# TK-BB-MD-07_vb.net
KiCad netlist of a schematic drawn in EAGLE
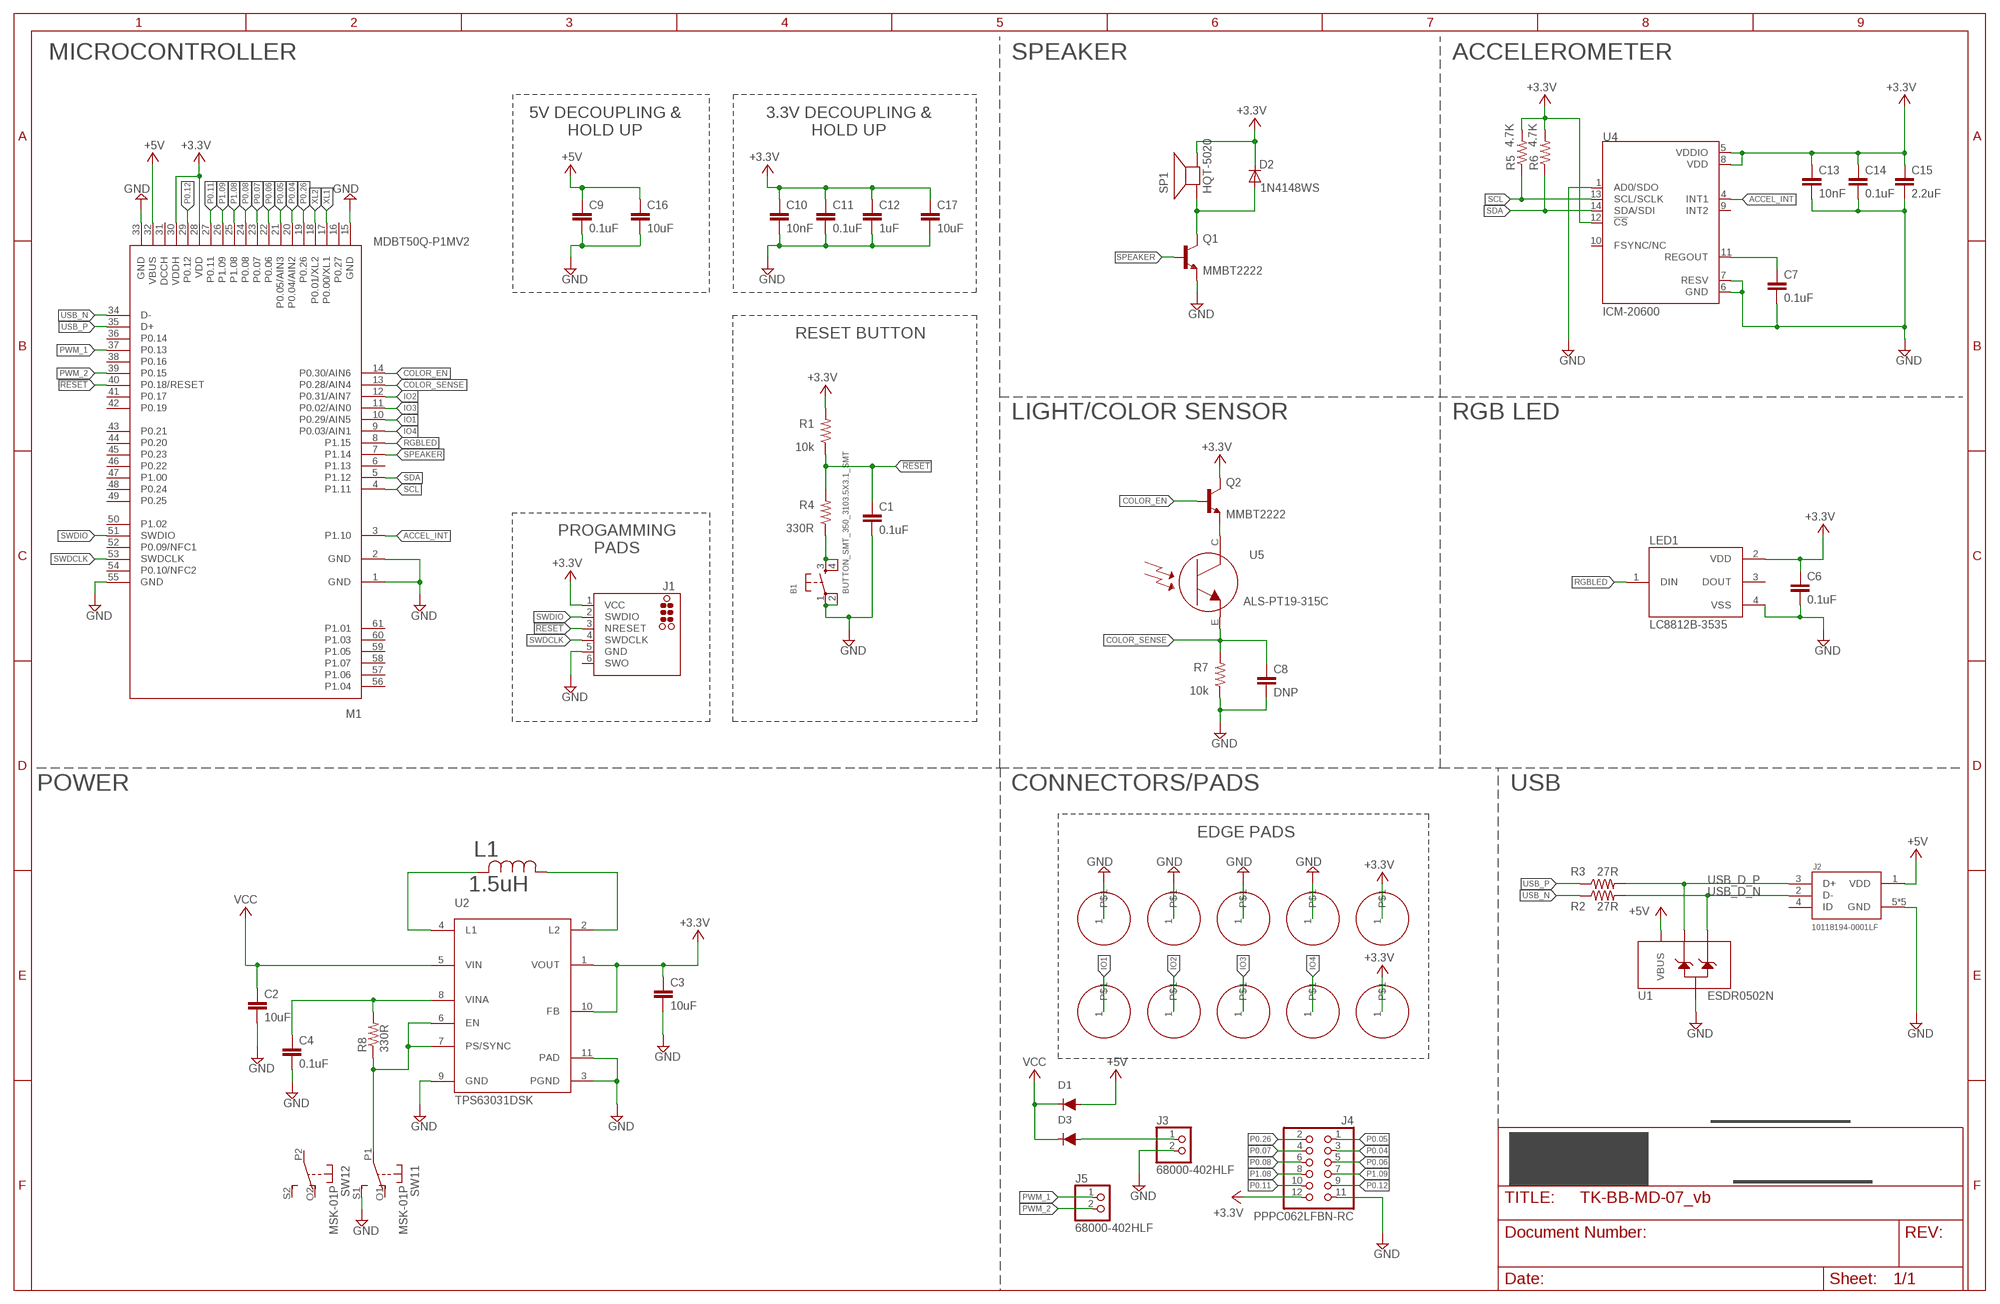
[diagram p0: schematic, sheet 1]

(export (version "E")
  (design (tool "Eeschema 10.0.6"))
  (components
    (comp (ref "B1")
      (value "BUTTON_SMT_350_3103.5X3.1_SMT")
      (footprint "eagle-import:3.5X3.1_SMT")
      (libsource (lib "eagle-import") (part "BUTTON_SMT_350_3103.5X3.1_SMT"))
    )
    (comp (ref "C1")
      (value "0.1uF")
      (footprint "eagle-import:0402")
      (fields
        (field (name "MANUFACTURER") "Yageo")
        (field (name "MANUFACTURER_PART_NUMBER") "CC0402KRX7R6BB104")
      )
      (libsource (lib "eagle-import") (part "C_0402_0.1UF_10V"))
    )
    (comp (ref "C2")
      (value "10uF")
      (footprint "eagle-import:0402")
      (fields
        (field (name "MANUFACTURER") "Samsung")
        (field (name "MANUFACTURER_PART_NUMBER") "CL05A106MP8NUB8")
      )
      (libsource (lib "eagle-import") (part "C_0402_10UF_10V"))
    )
    (comp (ref "C3")
      (value "10uF")
      (footprint "eagle-import:0402")
      (fields
        (field (name "MANUFACTURER") "Samsung")
        (field (name "MANUFACTURER_PART_NUMBER") "CL05A106MP8NUB8")
      )
      (libsource (lib "eagle-import") (part "C_0402_10UF_10V"))
    )
    (comp (ref "C4")
      (value "0.1uF")
      (footprint "eagle-import:0402")
      (fields
        (field (name "MANUFACTURER") "Yageo")
        (field (name "MANUFACTURER_PART_NUMBER") "CC0402KRX7R6BB104")
      )
      (libsource (lib "eagle-import") (part "C_0402_0.1UF_10V"))
    )
    (comp (ref "C6")
      (value "0.1uF")
      (footprint "eagle-import:0402")
      (fields
        (field (name "MANUFACTURER") "Yageo")
        (field (name "MANUFACTURER_PART_NUMBER") "CC0402KRX7R6BB104")
      )
      (libsource (lib "eagle-import") (part "C_0402_0.1UF_10V"))
    )
    (comp (ref "C7")
      (value "0.1uF")
      (footprint "eagle-import:0402")
      (fields
        (field (name "MANUFACTURER") "Yageo")
        (field (name "MANUFACTURER_PART_NUMBER") "CC0402KRX7R6BB104")
      )
      (libsource (lib "eagle-import") (part "C_0402_0.1UF_10V"))
    )
    (comp (ref "C8")
      (value "DNP")
      (footprint "eagle-import:0402")
      (libsource (lib "eagle-import") (part "C_0402_DNP"))
    )
    (comp (ref "C9")
      (value "0.1uF")
      (footprint "eagle-import:0402")
      (fields
        (field (name "MANUFACTURER") "Yageo")
        (field (name "MANUFACTURER_PART_NUMBER") "CC0402KRX7R6BB104")
      )
      (libsource (lib "eagle-import") (part "C_0402_0.1UF_10V"))
    )
    (comp (ref "C10")
      (value "10nF")
      (footprint "eagle-import:0402")
      (fields
        (field (name "MANUFACTURER") "Yageo")
        (field (name "MANUFACTURER_PART_NUMBER") "C0402C103K8RACTU")
      )
      (libsource (lib "eagle-import") (part "C_0402_10NF_10V"))
    )
    (comp (ref "C11")
      (value "0.1uF")
      (footprint "eagle-import:0402")
      (fields
        (field (name "MANUFACTURER") "Yageo")
        (field (name "MANUFACTURER_PART_NUMBER") "CC0402KRX7R6BB104")
      )
      (libsource (lib "eagle-import") (part "C_0402_0.1UF_10V"))
    )
    (comp (ref "C12")
      (value "1uF")
      (footprint "eagle-import:0402")
      (fields
        (field (name "MANUFACTURER") "Yageo")
        (field (name "MANUFACTURER_PART_NUMBER") "CC0402KRX5R6BB105")
      )
      (libsource (lib "eagle-import") (part "C_0402_1UF_10V"))
    )
    (comp (ref "C13")
      (value "10nF")
      (footprint "eagle-import:0402")
      (fields
        (field (name "MANUFACTURER") "Yageo")
        (field (name "MANUFACTURER_PART_NUMBER") "C0402C103K8RACTU")
      )
      (libsource (lib "eagle-import") (part "C_0402_10NF_10V"))
    )
    (comp (ref "C14")
      (value "0.1uF")
      (footprint "eagle-import:0402")
      (fields
        (field (name "MANUFACTURER") "Yageo")
        (field (name "MANUFACTURER_PART_NUMBER") "CC0402KRX7R6BB104")
      )
      (libsource (lib "eagle-import") (part "C_0402_0.1UF_10V"))
    )
    (comp (ref "C15")
      (value "2.2uF")
      (footprint "eagle-import:0402")
      (fields
        (field (name "MANUFACTURER") "Taiyo Yuden")
        (field (name "MANUFACTURER_PART_NUMBER") "LMK105BJ225MV-F")
      )
      (libsource (lib "eagle-import") (part "C_0402_2.2UF_10V"))
    )
    (comp (ref "C16")
      (value "10uF")
      (footprint "eagle-import:0402")
      (fields
        (field (name "MANUFACTURER") "Samsung")
        (field (name "MANUFACTURER_PART_NUMBER") "CL05A106MP8NUB8")
      )
      (libsource (lib "eagle-import") (part "C_0402_10UF_10V"))
    )
    (comp (ref "C17")
      (value "10uF")
      (footprint "eagle-import:0402")
      (fields
        (field (name "MANUFACTURER") "Samsung")
        (field (name "MANUFACTURER_PART_NUMBER") "CL05A106MP8NUB8")
      )
      (libsource (lib "eagle-import") (part "C_0402_10UF_10V"))
    )
    (comp (ref "D1")
      (value "NSR0320MW2T1G")
      (footprint "eagle-import:SOD323")
      (fields (field (name "MANUFACTURER") "ON Semiconductor"))
      (libsource (lib "eagle-import") (part "DIODE_SCHOTTKY_NSR0320MW2T1G"))
    )
    (comp (ref "D2")
      (value "1N4148WS")
      (footprint "eagle-import:SOD-323")
      (fields (field (name "MANUFACTURER") "ON Semiconductor"))
      (libsource (lib "eagle-import") (part "DIODESOD-323_1N148WS"))
    )
    (comp (ref "D3")
      (value "NSR0320MW2T1G")
      (footprint "eagle-import:SOD323")
      (fields (field (name "MANUFACTURER") "ON Semiconductor"))
      (libsource (lib "eagle-import") (part "DIODE_SCHOTTKY_NSR0320MW2T1G"))
    )
    (comp (ref "J1")
      (value "DNP")
      (footprint "eagle-import:TC2030-MCP-NL")
      (libsource (lib "eagle-import") (part "TC2030-MCP-NL"))
    )
    (comp (ref "J2")
      (value "10118194-0001LF")
      (footprint "eagle-import:10118194-0001LF")
      (fields (field (name "MANUFACTURER") "Amphenol"))
      (libsource (lib "eagle-import") (part "10118194-0001LF"))
    )
    (comp (ref "J3")
      (value "68000-402HLF")
      (footprint "eagle-import:1X02")
      (fields (field (name "MANUFACTURER") "Amphenol"))
      (libsource (lib "eagle-import") (part "PINHD-1X2"))
    )
    (comp (ref "J4")
      (value "PPPC062LFBN-RC")
      (footprint "eagle-import:2X06-F")
      (fields (field (name "MANUFACTURER") "Sullins Connector Solutions"))
      (libsource (lib "eagle-import") (part "PINHD-2X6-F"))
    )
    (comp (ref "J5")
      (value "68000-402HLF")
      (footprint "eagle-import:1X02")
      (fields (field (name "MANUFACTURER") "Amphenol"))
      (libsource (lib "eagle-import") (part "PINHD-1X2"))
    )
    (comp (ref "L1")
      (value "1.5uH")
      (footprint "eagle-import:INDC250X200X100")
      (fields
        (field (name "MANUFACTURER") "Delta Electronics/Cyntec")
        (field (name "MANUFACTURER_PART_NUMBER") "SDEM25201T-1R5MS")
      )
      (libsource (lib "eagle-import") (part "SDEM25201T-1R5MS"))
    )
    (comp (ref "LED1")
      (value "LC8812B-3535")
      (footprint "eagle-import:LC8812B-3535")
      (libsource (lib "eagle-import") (part "SK6812MINI_LC8812B-3535"))
    )
    (comp (ref "M1")
      (value "MDBT50Q-P1MV2")
      (footprint "eagle-import:MDBT50")
      (fields (field (name "MANUFACTURER") "Raytac"))
      (libsource (lib "eagle-import") (part "MDBT50Q-P1MV2"))
    )
    (comp (ref "P1")
      (value "BB_PADS_BANANA_ROUND")
      (footprint "eagle-import:BB_PAD_BANANA")
      (libsource (lib "eagle-import") (part "BB_PADS_BANANA_ROUND"))
    )
    (comp (ref "P2")
      (value "BB_PADS_BANANA_ROUND")
      (footprint "eagle-import:BB_PAD_BANANA")
      (libsource (lib "eagle-import") (part "BB_PADS_BANANA_ROUND"))
    )
    (comp (ref "P3")
      (value "BB_PADS_BANANA_ROUND")
      (footprint "eagle-import:BB_PAD_BANANA")
      (libsource (lib "eagle-import") (part "BB_PADS_BANANA_ROUND"))
    )
    (comp (ref "P4")
      (value "BB_PADS_BANANA_ROUND")
      (footprint "eagle-import:BB_PAD_BANANA")
      (libsource (lib "eagle-import") (part "BB_PADS_BANANA_ROUND"))
    )
    (comp (ref "P5")
      (value "BB_PADS_BANANA_ROUND")
      (footprint "eagle-import:BB_PAD_BANANA")
      (libsource (lib "eagle-import") (part "BB_PADS_BANANA_ROUND"))
    )
    (comp (ref "P6")
      (value "BB_PADS_BANANA_ROUND")
      (footprint "eagle-import:BB_PAD_BANANA")
      (libsource (lib "eagle-import") (part "BB_PADS_BANANA_ROUND"))
    )
    (comp (ref "P7")
      (value "BB_PADS_BANANA_ROUND")
      (footprint "eagle-import:BB_PAD_BANANA")
      (libsource (lib "eagle-import") (part "BB_PADS_BANANA_ROUND"))
    )
    (comp (ref "P8")
      (value "BB_PADS_BANANA_ROUND")
      (footprint "eagle-import:BB_PAD_BANANA")
      (libsource (lib "eagle-import") (part "BB_PADS_BANANA_ROUND"))
    )
    (comp (ref "P9")
      (value "BB_PADS_BANANA_ROUND")
      (footprint "eagle-import:BB_PAD_BANANA")
      (libsource (lib "eagle-import") (part "BB_PADS_BANANA_ROUND"))
    )
    (comp (ref "P10")
      (value "BB_PADS_BANANA_ROUND")
      (footprint "eagle-import:BB_PAD_BANANA")
      (libsource (lib "eagle-import") (part "BB_PADS_BANANA_ROUND"))
    )
    (comp (ref "Q1")
      (value "MMBT2222")
      (footprint "eagle-import:SOT23-WIDE")
      (fields
        (field (name "MANUFACTURER") "ON Semiconductor")
        (field (name "MANUFACTURER_PART_NUMBER") "MMBT2222LT1G")
      )
      (libsource (lib "eagle-import") (part "TRANSISTOR_NPN_WIDE_MMBT2222"))
    )
    (comp (ref "Q2")
      (value "MMBT2222")
      (footprint "eagle-import:SOT23-WIDE")
      (fields
        (field (name "MANUFACTURER") "ON Semiconductor")
        (field (name "MANUFACTURER_PART_NUMBER") "MMBT2222LT1G")
      )
      (libsource (lib "eagle-import") (part "TRANSISTOR_NPN_WIDE_MMBT2222"))
    )
    (comp (ref "R1")
      (value "10k")
      (footprint "eagle-import:0402")
      (fields
        (field (name "MANUFACTURER") "Yageo")
        (field (name "MANUFACTURER_PART_NUMBER") "RC0402JR-0710KL")
      )
      (libsource (lib "eagle-import") (part "R_0402_10K_0.0625W"))
    )
    (comp (ref "R2")
      (value "27R")
      (footprint "eagle-import:0402")
      (fields
        (field (name "MANUFACTURER") "Yageo")
        (field (name "MANUFACTURER_PART_NUMBER") "AC0402FR-0727RL")
      )
      (libsource (lib "eagle-import") (part "R_0402_27R_0.0625W"))
    )
    (comp (ref "R3")
      (value "27R")
      (footprint "eagle-import:0402")
      (fields
        (field (name "MANUFACTURER") "Yageo")
        (field (name "MANUFACTURER_PART_NUMBER") "AC0402FR-0727RL")
      )
      (libsource (lib "eagle-import") (part "R_0402_27R_0.0625W"))
    )
    (comp (ref "R4")
      (value "330R")
      (footprint "eagle-import:0402")
      (fields
        (field (name "MANUFACTURER") "Yageo")
        (field (name "MANUFACTURER_PART_NUMBER") "RC0402JR-07330RL")
      )
      (libsource (lib "eagle-import") (part "R_0402_330R_0.0625W"))
    )
    (comp (ref "R5")
      (value "4.7K")
      (footprint "eagle-import:0402")
      (fields
        (field (name "MANUFACTURER") "Yageo")
        (field (name "MANUFACTURER_PART_NUMBER") "RC0402JR-074K7L")
      )
      (libsource (lib "eagle-import") (part "R_0402_4.7K_0.0625W"))
    )
    (comp (ref "R6")
      (value "4.7K")
      (footprint "eagle-import:0402")
      (fields
        (field (name "MANUFACTURER") "Yageo")
        (field (name "MANUFACTURER_PART_NUMBER") "RC0402JR-074K7L")
      )
      (libsource (lib "eagle-import") (part "R_0402_4.7K_0.0625W"))
    )
    (comp (ref "R7")
      (value "10k")
      (footprint "eagle-import:0402")
      (fields
        (field (name "MANUFACTURER") "Panasonic")
        (field (name "MANUFACTURER_PART_NUMBER") "ERJ-2GEJ103X")
      )
      (libsource (lib "eagle-import") (part "R_0402_10K_0.1W"))
    )
    (comp (ref "R8")
      (value "330R")
      (footprint "eagle-import:0402")
      (fields
        (field (name "MANUFACTURER") "Yageo")
        (field (name "MANUFACTURER_PART_NUMBER") "RC0402JR-07330RL")
      )
      (libsource (lib "eagle-import") (part "R_0402_330R_0.0625W"))
    )
    (comp (ref "SP1")
      (value "HQT-5020")
      (footprint "eagle-import:HQT-5020")
      (libsource (lib "eagle-import") (part "SPEAKER_HQT-5020"))
    )
    (comp (ref "SW1")
      (value "MSK-01P")
      (footprint "eagle-import:MSK-01P")
      (fields (field (name "MANUFACTURER") "Shenzen Gangyuan Microkey Technology"))
      (libsource (lib "eagle-import") (part "DPDT_MSK-01P"))
    )
    (comp (ref "U1")
      (value "ESDR0502N")
      (footprint "eagle-import:6-UFDFN")
      (fields
        (field (name "MANUFACTURER") "ON Semiconductor")
        (field (name "MANUFACTURER_PART_NUMBER") "ESDR0502NMUTBG")
      )
      (libsource (lib "eagle-import") (part "ESDR0502N"))
    )
    (comp (ref "U2")
      (value "TPS63031DSK")
      (footprint "eagle-import:SON11P50_250X250X80")
      (fields
        (field (name "MANUFACTURER") "Texas Instruments")
        (field (name "MANUFACTURER_PART_NUMBER") "TPS63031DSKR")
      )
      (libsource (lib "eagle-import") (part "TPS63031DSKT"))
    )
    (comp (ref "U4")
      (value "ICM-20600")
      (footprint "eagle-import:ICM-20600")
      (fields (field (name "MANUFACTURER") "TDK-InvenSense"))
      (libsource (lib "eagle-import") (part "ICM-20600"))
    )
    (comp (ref "U5")
      (value "ALS-PT19-315C")
      (footprint "eagle-import:ALS-PT19-315C")
      (fields
        (field (name "MANUFACTURER") "Everlight Electronics Co Ltd")
        (field (name "MANUFACTURER_PART_NUMBER") "ALS-PT19-315C/L177/TR8")
      )
      (libsource (lib "eagle-import") (part "ALS-PT19-315C"))
    )
  )
  (nets
    (net (code "1") (name "+3.3V") (class "Default")
      (node (ref "C10") (pin "1") (pinfunction "1_1") (pintype "passive"))
      (node (ref "C11") (pin "1") (pinfunction "1_1") (pintype "passive"))
      (node (ref "C12") (pin "1") (pinfunction "1_1") (pintype "passive"))
      (node (ref "C13") (pin "1") (pinfunction "1_1") (pintype "passive"))
      (node (ref "C14") (pin "1") (pinfunction "1_1") (pintype "passive"))
      (node (ref "C15") (pin "1") (pinfunction "1_1") (pintype "passive"))
      (node (ref "C17") (pin "1") (pinfunction "1_1") (pintype "passive"))
      (node (ref "C3") (pin "1") (pinfunction "1_1") (pintype "passive"))
      (node (ref "C6") (pin "1") (pinfunction "1_1") (pintype "passive"))
      (node (ref "D2") (pin "C") (pinfunction "C_C") (pintype "passive"))
      (node (ref "J1") (pin "1") (pinfunction "VCC_1") (pintype "passive"))
      (node (ref "J4") (pin "12") (pinfunction "12_12") (pintype "passive"))
      (node (ref "LED1") (pin "2") (pinfunction "VDD_2") (pintype "power_in"))
      (node (ref "M1") (pin "28") (pinfunction "VDD_28") (pintype "bidirectional"))
      (node (ref "M1") (pin "30") (pinfunction "VDDH_30") (pintype "bidirectional"))
      (node (ref "P10") (pin "1") (pinfunction "P$1_1") (pintype "bidirectional"))
      (node (ref "P9") (pin "1") (pinfunction "P$1_1") (pintype "bidirectional"))
      (node (ref "Q2") (pin "3") (pinfunction "C_3") (pintype "passive"))
      (node (ref "R1") (pin "2") (pinfunction "2_2") (pintype "passive"))
      (node (ref "R5") (pin "2") (pinfunction "2_2") (pintype "passive"))
      (node (ref "R6") (pin "2") (pinfunction "2_2") (pintype "passive"))
      (node (ref "SP1") (pin "-") (pinfunction "-_-") (pintype "passive"))
      (node (ref "U2") (pin "1") (pinfunction "VOUT_1") (pintype "bidirectional"))
      (node (ref "U2") (pin "10") (pinfunction "FB_10") (pintype "bidirectional"))
      (node (ref "U4") (pin "12") (pinfunction "~{CS}_12") (pintype "input"))
      (node (ref "U4") (pin "5") (pinfunction "VDDIO_5") (pintype "power_in"))
      (node (ref "U4") (pin "8") (pinfunction "VDD_8") (pintype "power_in"))
    )
    (net (code "2") (name "+5V") (class "Default")
      (node (ref "C16") (pin "1") (pinfunction "1_1") (pintype "passive"))
      (node (ref "C9") (pin "1") (pinfunction "1_1") (pintype "passive"))
      (node (ref "D1") (pin "2") (pinfunction "A_2") (pintype "bidirectional"))
      (node (ref "J2") (pin "1") (pinfunction "VDD_1") (pintype "power_in"))
      (node (ref "M1") (pin "32") (pinfunction "VBUS_32") (pintype "bidirectional"))
      (node (ref "U1") (pin "P$6") (pinfunction "VBUS_P$6") (pintype "bidirectional"))
    )
    (net (code "3") (name "/USB_D_N") (class "Default")
      (node (ref "J2") (pin "2") (pinfunction "D-_2") (pintype "bidirectional"))
      (node (ref "R2") (pin "2") (pinfunction "2_2") (pintype "passive"))
      (node (ref "U1") (pin "P$3") (pinfunction "D-_P$3") (pintype "bidirectional"))
      (node (ref "U1") (pin "P$4") (pinfunction "D-_P$4") (pintype "bidirectional"))
    )
    (net (code "4") (name "/USB_D_P") (class "Default")
      (node (ref "J2") (pin "3") (pinfunction "D+_3") (pintype "bidirectional"))
      (node (ref "R3") (pin "2") (pinfunction "2_2") (pintype "passive"))
      (node (ref "U1") (pin "P$2") (pinfunction "D+_P$2") (pintype "bidirectional"))
      (node (ref "U1") (pin "P$5") (pinfunction "D+_P$5") (pintype "bidirectional"))
    )
    (net (code "5") (name "/~{RESET}") (class "Default")
      (node (ref "C1") (pin "1") (pinfunction "1_1") (pintype "passive"))
      (node (ref "J1") (pin "3") (pinfunction "NRESET_3") (pintype "power_in"))
      (node (ref "M1") (pin "40") (pinfunction "P0.18/RESET_40") (pintype "bidirectional"))
      (node (ref "R1") (pin "1") (pinfunction "1_1") (pintype "passive"))
      (node (ref "R4") (pin "2") (pinfunction "2_2") (pintype "passive"))
    )
    (net (code "6") (name "ACCEL_INT") (class "Default")
      (node (ref "M1") (pin "3") (pinfunction "P1.10_3") (pintype "bidirectional"))
      (node (ref "U4") (pin "4") (pinfunction "INT1_4") (pintype "output"))
    )
    (net (code "7") (name "COLOR_EN") (class "Default")
      (node (ref "M1") (pin "14") (pinfunction "P0.30/AIN6_14") (pintype "bidirectional"))
      (node (ref "Q2") (pin "1") (pinfunction "B_1") (pintype "passive"))
    )
    (net (code "8") (name "COLOR_SENSE") (class "Default")
      (node (ref "C8") (pin "1") (pinfunction "1_1") (pintype "passive"))
      (node (ref "M1") (pin "13") (pinfunction "P0.28/AIN4_13") (pintype "bidirectional"))
      (node (ref "R7") (pin "2") (pinfunction "2_2") (pintype "passive"))
      (node (ref "U5") (pin "E") (pinfunction "E_E") (pintype "bidirectional"))
    )
    (net (code "9") (name "GND") (class "Default")
      (node (ref "B1") (pin "1") (pinfunction "P_1") (pintype "passive"))
      (node (ref "B1") (pin "2") (pinfunction "P1_2") (pintype "passive"))
      (node (ref "C1") (pin "2") (pinfunction "2_2") (pintype "passive"))
      (node (ref "C10") (pin "2") (pinfunction "2_2") (pintype "passive"))
      (node (ref "C11") (pin "2") (pinfunction "2_2") (pintype "passive"))
      (node (ref "C12") (pin "2") (pinfunction "2_2") (pintype "passive"))
      (node (ref "C13") (pin "2") (pinfunction "2_2") (pintype "passive"))
      (node (ref "C14") (pin "2") (pinfunction "2_2") (pintype "passive"))
      (node (ref "C15") (pin "2") (pinfunction "2_2") (pintype "passive"))
      (node (ref "C16") (pin "2") (pinfunction "2_2") (pintype "passive"))
      (node (ref "C17") (pin "2") (pinfunction "2_2") (pintype "passive"))
      (node (ref "C2") (pin "2") (pinfunction "2_2") (pintype "passive"))
      (node (ref "C3") (pin "2") (pinfunction "2_2") (pintype "passive"))
      (node (ref "C4") (pin "2") (pinfunction "2_2") (pintype "passive"))
      (node (ref "C6") (pin "2") (pinfunction "2_2") (pintype "passive"))
      (node (ref "C7") (pin "2") (pinfunction "2_2") (pintype "passive"))
      (node (ref "C8") (pin "2") (pinfunction "2_2") (pintype "passive"))
      (node (ref "C9") (pin "2") (pinfunction "2_2") (pintype "passive"))
      (node (ref "J1") (pin "5") (pinfunction "GND_5") (pintype "output"))
      (node (ref "J2") (pin "5") (pinfunction "GND_5") (pintype "power_in"))
      (node (ref "J2") (pin "P$6") (pinfunction "GND_P$6") (pintype "power_in"))
      (node (ref "J2") (pin "P$7") (pinfunction "GND_P$7") (pintype "power_in"))
      (node (ref "J2") (pin "P$8") (pinfunction "GND_P$8") (pintype "power_in"))
      (node (ref "J2") (pin "P$9") (pinfunction "GND_P$9") (pintype "power_in"))
      (node (ref "J3") (pin "2") (pinfunction "2_2") (pintype "passive"))
      (node (ref "J4") (pin "11") (pinfunction "11_11") (pintype "passive"))
      (node (ref "LED1") (pin "4") (pinfunction "VSS_4") (pintype "power_in"))
      (node (ref "M1") (pin "1") (pinfunction "GND_1") (pintype "bidirectional"))
      (node (ref "M1") (pin "15") (pinfunction "GND_15") (pintype "bidirectional"))
      (node (ref "M1") (pin "2") (pinfunction "GND_2") (pintype "bidirectional"))
      (node (ref "M1") (pin "33") (pinfunction "GND_33") (pintype "bidirectional"))
      (node (ref "M1") (pin "55") (pinfunction "GND_55") (pintype "bidirectional"))
      (node (ref "P1") (pin "1") (pinfunction "P$1_1") (pintype "bidirectional"))
      (node (ref "P2") (pin "1") (pinfunction "P$1_1") (pintype "bidirectional"))
      (node (ref "P3") (pin "1") (pinfunction "P$1_1") (pintype "bidirectional"))
      (node (ref "P8") (pin "1") (pinfunction "P$1_1") (pintype "bidirectional"))
      (node (ref "Q1") (pin "2") (pinfunction "E_2") (pintype "passive"))
      (node (ref "R7") (pin "1") (pinfunction "1_1") (pintype "passive"))
      (node (ref "SW1") (pin "S1") (pinfunction "S_S1") (pintype "passive"))
      (node (ref "U1") (pin "P$1") (pinfunction "GND_P$1") (pintype "bidirectional"))
      (node (ref "U2") (pin "11") (pinfunction "PAD_11") (pintype "bidirectional"))
      (node (ref "U2") (pin "3") (pinfunction "PGND_3") (pintype "bidirectional"))
      (node (ref "U2") (pin "9") (pinfunction "GND_9") (pintype "bidirectional"))
      (node (ref "U4") (pin "1") (pinfunction "AD0/SDO_1") (pintype "output"))
      (node (ref "U4") (pin "6") (pinfunction "GND_6") (pintype "power_in"))
      (node (ref "U4") (pin "7") (pinfunction "RESV_7") (pintype "power_in"))
    )
    (net (code "10") (name "IO1") (class "Default")
      (node (ref "M1") (pin "10") (pinfunction "P0.29/AIN5_10") (pintype "bidirectional"))
      (node (ref "P6") (pin "1") (pinfunction "P$1_1") (pintype "bidirectional"))
    )
    (net (code "11") (name "IO2") (class "Default")
      (node (ref "M1") (pin "12") (pinfunction "P0.31/AIN7_12") (pintype "bidirectional"))
      (node (ref "P4") (pin "1") (pinfunction "P$1_1") (pintype "bidirectional"))
    )
    (net (code "12") (name "IO3") (class "Default")
      (node (ref "M1") (pin "11") (pinfunction "P0.02/AIN0_11") (pintype "bidirectional"))
      (node (ref "P7") (pin "1") (pinfunction "P$1_1") (pintype "bidirectional"))
    )
    (net (code "13") (name "IO4") (class "Default")
      (node (ref "M1") (pin "9") (pinfunction "P0.03/AIN1_9") (pintype "bidirectional"))
      (node (ref "P5") (pin "1") (pinfunction "P$1_1") (pintype "bidirectional"))
    )
    (net (code "14") (name "Net-(B1-S)") (class "Default")
      (node (ref "B1") (pin "3") (pinfunction "S_3") (pintype "passive"))
      (node (ref "B1") (pin "4") (pinfunction "S1_4") (pintype "passive"))
      (node (ref "R4") (pin "1") (pinfunction "1_1") (pintype "passive"))
    )
    (net (code "15") (name "Net-(D3-A)") (class "Default")
      (node (ref "D3") (pin "2") (pinfunction "A_2") (pintype "bidirectional"))
      (node (ref "J3") (pin "1") (pinfunction "1_1") (pintype "passive"))
    )
    (net (code "16") (name "Net-(Q1-C)") (class "Default")
      (node (ref "D2") (pin "A") (pinfunction "A_A") (pintype "passive"))
      (node (ref "Q1") (pin "3") (pinfunction "C_3") (pintype "passive"))
      (node (ref "SP1") (pin "+") (pinfunction "+_+") (pintype "passive"))
    )
    (net (code "17") (name "Net-(Q2-E)") (class "Default")
      (node (ref "Q2") (pin "2") (pinfunction "E_2") (pintype "passive"))
      (node (ref "U5") (pin "C") (pinfunction "C_C") (pintype "bidirectional"))
    )
    (net (code "18") (name "Net-(SW1A-P)") (class "Default")
      (node (ref "R8") (pin "1") (pinfunction "1_1") (pintype "passive"))
      (node (ref "SW1") (pin "P1") (pinfunction "P_P1") (pintype "passive"))
      (node (ref "U2") (pin "6") (pinfunction "EN_6") (pintype "bidirectional"))
      (node (ref "U2") (pin "7") (pinfunction "PS/SYNC_7") (pintype "bidirectional"))
    )
    (net (code "19") (name "Net-(U2-L1)") (class "Default")
      (node (ref "L1") (pin "2") (pinfunction "2_2") (pintype "passive"))
      (node (ref "U2") (pin "4") (pinfunction "L1_4") (pintype "bidirectional"))
    )
    (net (code "20") (name "Net-(U2-L2)") (class "Default")
      (node (ref "L1") (pin "1") (pinfunction "1_1") (pintype "passive"))
      (node (ref "U2") (pin "2") (pinfunction "L2_2") (pintype "bidirectional"))
    )
    (net (code "21") (name "Net-(U2-VINA)") (class "Default")
      (node (ref "C4") (pin "1") (pinfunction "1_1") (pintype "passive"))
      (node (ref "R8") (pin "2") (pinfunction "2_2") (pintype "passive"))
      (node (ref "U2") (pin "8") (pinfunction "VINA_8") (pintype "bidirectional"))
    )
    (net (code "22") (name "Net-(U4-REGOUT)") (class "Default")
      (node (ref "C7") (pin "1") (pinfunction "1_1") (pintype "passive"))
      (node (ref "U4") (pin "11") (pinfunction "REGOUT_11") (pintype "passive"))
    )
    (net (code "23") (name "P0.04") (class "Default")
      (node (ref "J4") (pin "3") (pinfunction "3_3") (pintype "passive"))
      (node (ref "M1") (pin "20") (pinfunction "P0.04/AIN2_20") (pintype "bidirectional"))
    )
    (net (code "24") (name "P0.05") (class "Default")
      (node (ref "J4") (pin "1") (pinfunction "1_1") (pintype "passive"))
      (node (ref "M1") (pin "21") (pinfunction "P0.05/AIN3_21") (pintype "bidirectional"))
    )
    (net (code "25") (name "P0.06") (class "Default")
      (node (ref "J4") (pin "5") (pinfunction "5_5") (pintype "passive"))
      (node (ref "M1") (pin "22") (pinfunction "P0.06_22") (pintype "bidirectional"))
    )
    (net (code "26") (name "P0.07") (class "Default")
      (node (ref "J4") (pin "4") (pinfunction "4_4") (pintype "passive"))
      (node (ref "M1") (pin "23") (pinfunction "P0.07_23") (pintype "bidirectional"))
    )
    (net (code "27") (name "P0.08") (class "Default")
      (node (ref "J4") (pin "6") (pinfunction "6_6") (pintype "passive"))
      (node (ref "M1") (pin "24") (pinfunction "P0.08_24") (pintype "bidirectional"))
    )
    (net (code "28") (name "P0.11") (class "Default")
      (node (ref "J4") (pin "10") (pinfunction "10_10") (pintype "passive"))
      (node (ref "M1") (pin "27") (pinfunction "P0.11_27") (pintype "bidirectional"))
    )
    (net (code "29") (name "P0.12") (class "Default")
      (node (ref "J4") (pin "9") (pinfunction "9_9") (pintype "passive"))
      (node (ref "M1") (pin "29") (pinfunction "P0.12_29") (pintype "bidirectional"))
    )
    (net (code "30") (name "P0.26") (class "Default")
      (node (ref "J4") (pin "2") (pinfunction "2_2") (pintype "passive"))
      (node (ref "M1") (pin "19") (pinfunction "P0.26_19") (pintype "bidirectional"))
    )
    (net (code "31") (name "P1.08") (class "Default")
      (node (ref "J4") (pin "8") (pinfunction "8_8") (pintype "passive"))
      (node (ref "M1") (pin "25") (pinfunction "P1.08_25") (pintype "bidirectional"))
    )
    (net (code "32") (name "P1.09") (class "Default")
      (node (ref "J4") (pin "7") (pinfunction "7_7") (pintype "passive"))
      (node (ref "M1") (pin "26") (pinfunction "P1.09_26") (pintype "bidirectional"))
    )
    (net (code "33") (name "PWM_1") (class "Default")
      (node (ref "J5") (pin "1") (pinfunction "1_1") (pintype "passive"))
      (node (ref "M1") (pin "37") (pinfunction "P0.13_37") (pintype "bidirectional"))
    )
    (net (code "34") (name "PWM_2") (class "Default")
      (node (ref "J5") (pin "2") (pinfunction "2_2") (pintype "passive"))
      (node (ref "M1") (pin "39") (pinfunction "P0.15_39") (pintype "bidirectional"))
    )
    (net (code "35") (name "RGBLED") (class "Default")
      (node (ref "LED1") (pin "1") (pinfunction "DIN_1") (pintype "input"))
      (node (ref "M1") (pin "8") (pinfunction "P1.15_8") (pintype "bidirectional"))
    )
    (net (code "36") (name "SCL") (class "Default")
      (node (ref "M1") (pin "4") (pinfunction "P1.11_4") (pintype "bidirectional"))
      (node (ref "R5") (pin "1") (pinfunction "1_1") (pintype "passive"))
      (node (ref "U4") (pin "13") (pinfunction "SCL/SCLK_13") (pintype "bidirectional"))
    )
    (net (code "37") (name "SDA") (class "Default")
      (node (ref "M1") (pin "5") (pinfunction "P1.12_5") (pintype "bidirectional"))
      (node (ref "R6") (pin "1") (pinfunction "1_1") (pintype "passive"))
      (node (ref "U4") (pin "14") (pinfunction "SDA/SDI_14") (pintype "bidirectional"))
    )
    (net (code "38") (name "SPEAKER") (class "Default")
      (node (ref "M1") (pin "7") (pinfunction "P1.14_7") (pintype "bidirectional"))
      (node (ref "Q1") (pin "1") (pinfunction "B_1") (pintype "passive"))
    )
    (net (code "39") (name "SWDCLK") (class "Default")
      (node (ref "J1") (pin "4") (pinfunction "SWDCLK_4") (pintype "bidirectional"))
      (node (ref "M1") (pin "53") (pinfunction "SWDCLK_53") (pintype "bidirectional"))
    )
    (net (code "40") (name "SWDIO") (class "Default")
      (node (ref "J1") (pin "2") (pinfunction "SWDIO_2") (pintype "power_in"))
      (node (ref "M1") (pin "51") (pinfunction "SWDIO_51") (pintype "bidirectional"))
    )
    (net (code "41") (name "USB_N") (class "Default")
      (node (ref "M1") (pin "34") (pinfunction "D-_34") (pintype "bidirectional"))
      (node (ref "R2") (pin "1") (pinfunction "1_1") (pintype "passive"))
    )
    (net (code "42") (name "USB_P") (class "Default")
      (node (ref "M1") (pin "35") (pinfunction "D+_35") (pintype "bidirectional"))
      (node (ref "R3") (pin "1") (pinfunction "1_1") (pintype "passive"))
    )
    (net (code "43") (name "VCC") (class "Default")
      (node (ref "C2") (pin "1") (pinfunction "1_1") (pintype "passive"))
      (node (ref "D1") (pin "1") (pinfunction "C_1") (pintype "bidirectional"))
      (node (ref "D3") (pin "1") (pinfunction "C_1") (pintype "bidirectional"))
      (node (ref "U2") (pin "5") (pinfunction "VIN_5") (pintype "bidirectional"))
    )
    (net (code "44") (name "XL1") (class "Default")
      (node (ref "M1") (pin "17") (pinfunction "P0.00/XL1_17") (pintype "bidirectional"))
    )
    (net (code "45") (name "XL2") (class "Default")
      (node (ref "M1") (pin "18") (pinfunction "P0.01/XL2_18") (pintype "bidirectional"))
    )
    (net (code "46") (name "unconnected-(J1-SWO-Pad6)") (class "Default")
      (node (ref "J1") (pin "6") (pinfunction "SWO_6") (pintype "bidirectional"))
    )
    (net (code "47") (name "unconnected-(J2-ID-Pad4)") (class "Default")
      (node (ref "J2") (pin "4") (pinfunction "ID_4") (pintype "passive"))
    )
    (net (code "48") (name "unconnected-(LED1-DOUT-Pad3)") (class "Default")
      (node (ref "LED1") (pin "3") (pinfunction "DOUT_3") (pintype "output"))
    )
    (net (code "49") (name "unconnected-(M1-DCCH-Pad31)") (class "Default")
      (node (ref "M1") (pin "31") (pinfunction "DCCH_31") (pintype "bidirectional"))
    )
    (net (code "50") (name "unconnected-(M1-P0.09{slash}NFC1-Pad52)") (class "Default")
      (node (ref "M1") (pin "52") (pinfunction "P0.09/NFC1_52") (pintype "bidirectional"))
    )
    (net (code "51") (name "unconnected-(M1-P0.10{slash}NFC2-Pad54)") (class "Default")
      (node (ref "M1") (pin "54") (pinfunction "P0.10/NFC2_54") (pintype "bidirectional"))
    )
    (net (code "52") (name "unconnected-(M1-P0.14-Pad36)") (class "Default")
      (node (ref "M1") (pin "36") (pinfunction "P0.14_36") (pintype "bidirectional"))
    )
    (net (code "53") (name "unconnected-(M1-P0.16-Pad38)") (class "Default")
      (node (ref "M1") (pin "38") (pinfunction "P0.16_38") (pintype "bidirectional"))
    )
    (net (code "54") (name "unconnected-(M1-P0.17-Pad41)") (class "Default")
      (node (ref "M1") (pin "41") (pinfunction "P0.17_41") (pintype "bidirectional"))
    )
    (net (code "55") (name "unconnected-(M1-P0.19-Pad42)") (class "Default")
      (node (ref "M1") (pin "42") (pinfunction "P0.19_42") (pintype "bidirectional"))
    )
    (net (code "56") (name "unconnected-(M1-P0.20-Pad44)") (class "Default")
      (node (ref "M1") (pin "44") (pinfunction "P0.20_44") (pintype "bidirectional"))
    )
    (net (code "57") (name "unconnected-(M1-P0.21-Pad43)") (class "Default")
      (node (ref "M1") (pin "43") (pinfunction "P0.21_43") (pintype "bidirectional"))
    )
    (net (code "58") (name "unconnected-(M1-P0.22-Pad46)") (class "Default")
      (node (ref "M1") (pin "46") (pinfunction "P0.22_46") (pintype "bidirectional"))
    )
    (net (code "59") (name "unconnected-(M1-P0.23-Pad45)") (class "Default")
      (node (ref "M1") (pin "45") (pinfunction "P0.23_45") (pintype "bidirectional"))
    )
    (net (code "60") (name "unconnected-(M1-P0.24-Pad48)") (class "Default")
      (node (ref "M1") (pin "48") (pinfunction "P0.24_48") (pintype "bidirectional"))
    )
    (net (code "61") (name "unconnected-(M1-P0.25-Pad49)") (class "Default")
      (node (ref "M1") (pin "49") (pinfunction "P0.25_49") (pintype "bidirectional"))
    )
    (net (code "62") (name "unconnected-(M1-P0.27-Pad16)") (class "Default")
      (node (ref "M1") (pin "16") (pinfunction "P0.27_16") (pintype "bidirectional"))
    )
    (net (code "63") (name "unconnected-(M1-P1.00-Pad47)") (class "Default")
      (node (ref "M1") (pin "47") (pinfunction "P1.00_47") (pintype "bidirectional"))
    )
    (net (code "64") (name "unconnected-(M1-P1.01-Pad61)") (class "Default")
      (node (ref "M1") (pin "61") (pinfunction "P1.01_61") (pintype "bidirectional"))
    )
    (net (code "65") (name "unconnected-(M1-P1.02-Pad50)") (class "Default")
      (node (ref "M1") (pin "50") (pinfunction "P1.02_50") (pintype "bidirectional"))
    )
    (net (code "66") (name "unconnected-(M1-P1.03-Pad60)") (class "Default")
      (node (ref "M1") (pin "60") (pinfunction "P1.03_60") (pintype "bidirectional"))
    )
    (net (code "67") (name "unconnected-(M1-P1.04-Pad56)") (class "Default")
      (node (ref "M1") (pin "56") (pinfunction "P1.04_56") (pintype "bidirectional"))
    )
    (net (code "68") (name "unconnected-(M1-P1.05-Pad59)") (class "Default")
      (node (ref "M1") (pin "59") (pinfunction "P1.05_59") (pintype "bidirectional"))
    )
    (net (code "69") (name "unconnected-(M1-P1.06-Pad57)") (class "Default")
      (node (ref "M1") (pin "57") (pinfunction "P1.06_57") (pintype "bidirectional"))
    )
    (net (code "70") (name "unconnected-(M1-P1.07-Pad58)") (class "Default")
      (node (ref "M1") (pin "58") (pinfunction "P1.07_58") (pintype "bidirectional"))
    )
    (net (code "71") (name "unconnected-(M1-P1.13-Pad6)") (class "Default")
      (node (ref "M1") (pin "6") (pinfunction "P1.13_6") (pintype "bidirectional"))
    )
    (net (code "72") (name "unconnected-(SW1A-O-PadO1)") (class "Default")
      (node (ref "SW1") (pin "O1") (pinfunction "O_O1") (pintype "passive"))
    )
    (net (code "73") (name "unconnected-(SW1B-O-PadO2)") (class "Default")
      (node (ref "SW1") (pin "O2") (pinfunction "O_O2") (pintype "passive"))
    )
    (net (code "74") (name "unconnected-(SW1B-P-PadP2)") (class "Default")
      (node (ref "SW1") (pin "P2") (pinfunction "P_P2") (pintype "passive"))
    )
    (net (code "75") (name "unconnected-(SW1B-S-PadS2)") (class "Default")
      (node (ref "SW1") (pin "S2") (pinfunction "S_S2") (pintype "passive"))
    )
    (net (code "76") (name "unconnected-(U4-FSYNC{slash}NC-Pad10)") (class "Default")
      (node (ref "U4") (pin "10") (pinfunction "FSYNC/NC_10") (pintype "input"))
    )
    (net (code "77") (name "unconnected-(U4-INT2-Pad9)") (class "Default")
      (node (ref "U4") (pin "9") (pinfunction "INT2_9") (pintype "output"))
    )
  )
)
